# AphelionGroundStation.net
KiCad netlist of a schematic drawn in Altium Designer
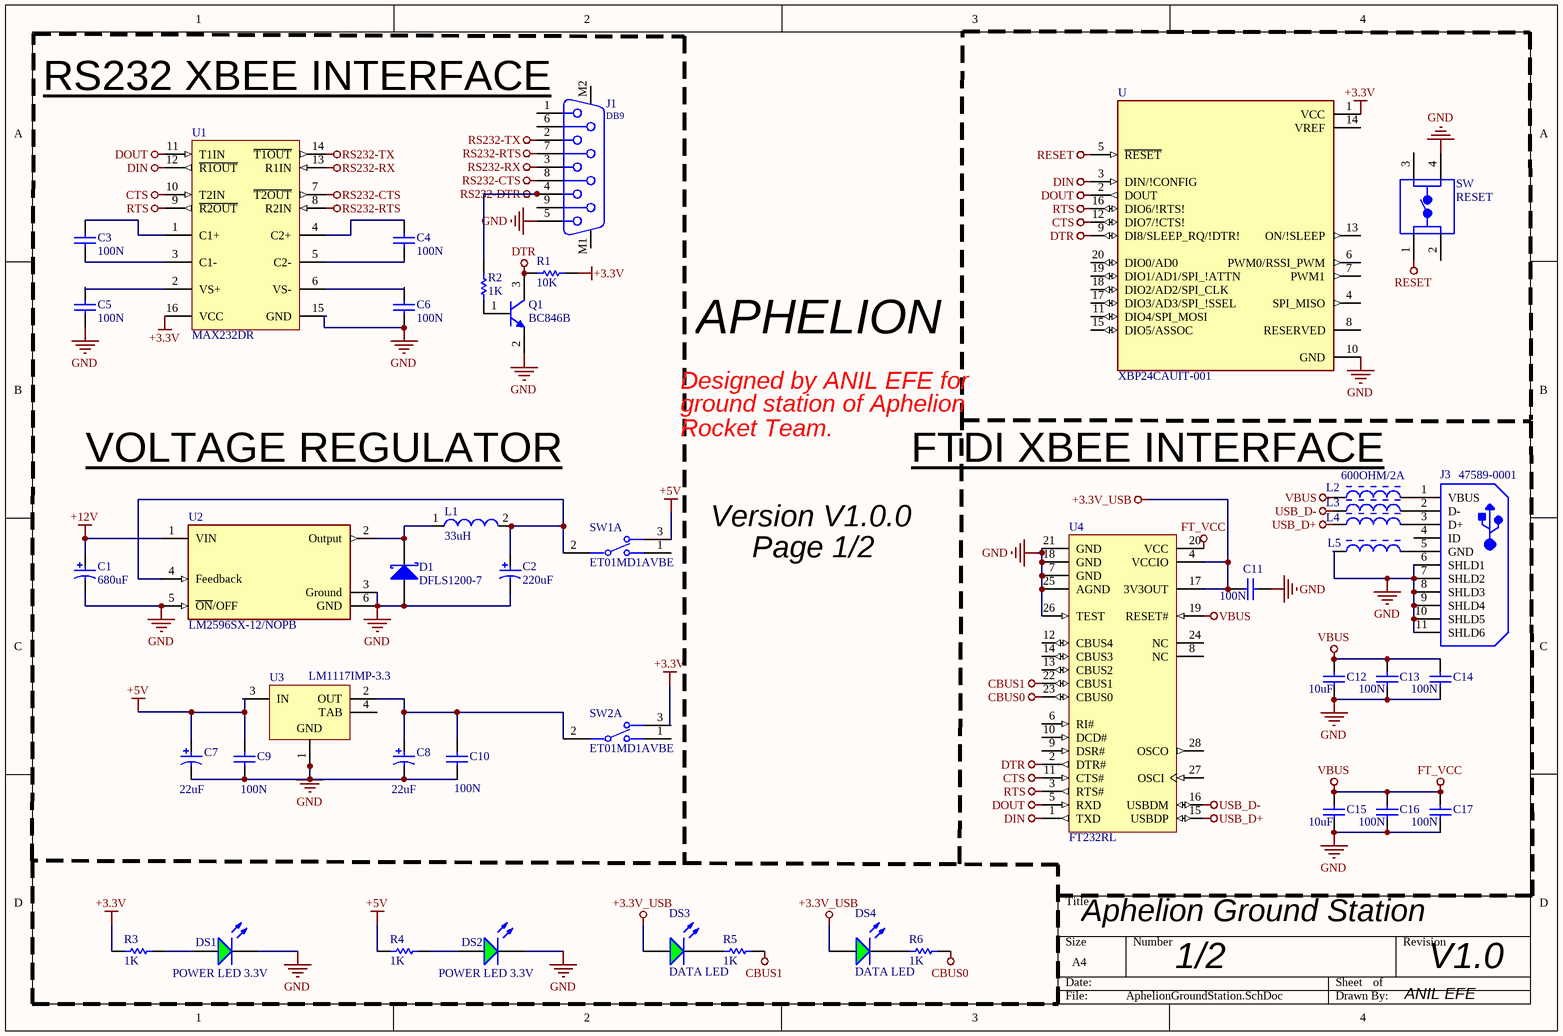
[diagram p0: AphelionGroundStation.SchDoc]

(export (version "E")
  (design (tool "Eeschema 10.0.6"))
  (components
    (comp (ref "C1")
      (value "680uF")
      (footprint "PNSC-FT-V-G_V")
      (fields (field (name "MANUFACTURER") "Panasonic"))
      (libsource (lib "Altium Content Vault") (part "CAP-P-2"))
    )
    (comp (ref "C2")
      (value "220uF")
      (footprint "PNSC-FP-V-F_V")
      (fields (field (name "MANUFACTURER") "Panasonic"))
      (libsource (lib "Altium Content Vault") (part "CAP-P-2"))
    )
    (comp (ref "C3")
      (value "100N")
      (footprint "KEMT-1206-2_M")
      (description "CAP, Ceramic, 0.1 uF, +/- 10%, 50 V, -55 to 125 degC, 1206 (3216 Metric), RoHS, Tape and Reel")
      (fields (field (name "MANUFACTURER") "Kemet"))
      (libsource (lib "Altium Content Vault") (part "CAP-NP-2"))
    )
    (comp (ref "C4")
      (value "100N")
      (footprint "KEMT-1206-2_M")
      (description "CAP, Ceramic, 0.1 uF, +/- 10%, 50 V, -55 to 125 degC, 1206 (3216 Metric), RoHS, Tape and Reel")
      (fields (field (name "MANUFACTURER") "Kemet"))
      (libsource (lib "Altium Content Vault") (part "CAP-NP-2"))
    )
    (comp (ref "C5")
      (value "100N")
      (footprint "KEMT-1206-2_M")
      (description "CAP, Ceramic, 0.1 uF, +/- 10%, 50 V, -55 to 125 degC, 1206 (3216 Metric), RoHS, Tape and Reel")
      (fields (field (name "MANUFACTURER") "Kemet"))
      (libsource (lib "Altium Content Vault") (part "CAP-NP-2"))
    )
    (comp (ref "C6")
      (value "100N")
      (footprint "KEMT-1206-2_M")
      (description "CAP, Ceramic, 0.1 uF, +/- 10%, 50 V, -55 to 125 degC, 1206 (3216 Metric), RoHS, Tape and Reel")
      (fields (field (name "MANUFACTURER") "Kemet"))
      (libsource (lib "Altium Content Vault") (part "CAP-NP-2"))
    )
    (comp (ref "C7")
      (value "22uF")
      (footprint "KEMT-T491-D_L")
      (fields (field (name "MANUFACTURER") "Kemet"))
      (libsource (lib "Altium Content Vault") (part "CAP-P-2"))
    )
    (comp (ref "C8")
      (value "22uF")
      (footprint "KEMT-T491-D_L")
      (fields (field (name "MANUFACTURER") "Kemet"))
      (libsource (lib "Altium Content Vault") (part "CAP-P-2"))
    )
    (comp (ref "C9")
      (value "100N")
      (footprint "KEMT-1206-2_M")
      (description "CAP, Ceramic, 0.1 uF, +/- 10%, 50 V, -55 to 125 degC, 1206 (3216 Metric), RoHS, Tape and Reel")
      (fields (field (name "MANUFACTURER") "Kemet"))
      (libsource (lib "Altium Content Vault") (part "CAP-NP-2"))
    )
    (comp (ref "C10")
      (value "100N")
      (footprint "KEMT-1206-2_M")
      (description "CAP, Ceramic, 0.1 uF, +/- 10%, 50 V, -55 to 125 degC, 1206 (3216 Metric), RoHS, Tape and Reel")
      (fields (field (name "MANUFACTURER") "Kemet"))
      (libsource (lib "Altium Content Vault") (part "CAP-NP-2"))
    )
    (comp (ref "C11")
      (value "100N")
      (footprint "KEMT-1206-2_M")
      (description "CAP, Ceramic, 0.1 uF, +/- 10%, 50 V, -55 to 125 degC, 1206 (3216 Metric), RoHS, Tape and Reel")
      (fields (field (name "MANUFACTURER") "Kemet"))
      (libsource (lib "Altium Content Vault") (part "CAP-NP-2"))
    )
    (comp (ref "C12")
      (value "10uF")
      (footprint "KEMT-1206-2_M")
      (description "CAP, Ceramic, 0.1 uF, +/- 10%, 50 V, -55 to 125 degC, 1206 (3216 Metric), RoHS, Tape and Reel")
      (fields (field (name "MANUFACTURER") "Kemet"))
      (libsource (lib "Altium Content Vault") (part "CAP-NP-2"))
    )
    (comp (ref "C13")
      (value "100N")
      (footprint "KEMT-1206-2_M")
      (description "CAP, Ceramic, 0.1 uF, +/- 10%, 50 V, -55 to 125 degC, 1206 (3216 Metric), RoHS, Tape and Reel")
      (fields (field (name "MANUFACTURER") "Kemet"))
      (libsource (lib "Altium Content Vault") (part "CAP-NP-2"))
    )
    (comp (ref "C14")
      (value "100N")
      (footprint "KEMT-1206-2_M")
      (description "CAP, Ceramic, 0.1 uF, +/- 10%, 50 V, -55 to 125 degC, 1206 (3216 Metric), RoHS, Tape and Reel")
      (fields (field (name "MANUFACTURER") "Kemet"))
      (libsource (lib "Altium Content Vault") (part "CAP-NP-2"))
    )
    (comp (ref "C15")
      (value "10uF")
      (footprint "KEMT-1206-2_M")
      (description "CAP, Ceramic, 0.1 uF, +/- 10%, 50 V, -55 to 125 degC, 1206 (3216 Metric), RoHS, Tape and Reel")
      (fields (field (name "MANUFACTURER") "Kemet"))
      (libsource (lib "Altium Content Vault") (part "CAP-NP-2"))
    )
    (comp (ref "C16")
      (value "100N")
      (footprint "KEMT-1206-2_M")
      (description "CAP, Ceramic, 0.1 uF, +/- 10%, 50 V, -55 to 125 degC, 1206 (3216 Metric), RoHS, Tape and Reel")
      (fields (field (name "MANUFACTURER") "Kemet"))
      (libsource (lib "Altium Content Vault") (part "CAP-NP-2"))
    )
    (comp (ref "C17")
      (value "100N")
      (footprint "KEMT-1206-2_M")
      (description "CAP, Ceramic, 0.1 uF, +/- 10%, 50 V, -55 to 125 degC, 1206 (3216 Metric), RoHS, Tape and Reel")
      (fields (field (name "MANUFACTURER") "Kemet"))
      (libsource (lib "Altium Content Vault") (part "CAP-NP-2"))
    )
    (comp (ref "D1")
      (value "DFLS1200-7")
      (footprint "DIOD-POWERDI123-2_A_V")
      (fields (field (name "MANUFACTURER") "Diodes Inc"))
      (libsource (lib "Altium Content Vault") (part "DSKY-AK-2"))
    )
    (comp (ref "DS1")
      (value "POWER LED 3.3V")
      (footprint "KING-APTD3216CGCK_V")
      (description "Chip LED Lamp, Green, 5 V, 30 mA, -40 to 85 degC, 2-Pin SMD, RoHS, Tape and Reel")
      (fields (field (name "MANUFACTURER") "Kingbright"))
      (libsource (lib "Altium Content Vault") (part "LED-GREEN-AK-2"))
    )
    (comp (ref "DS2")
      (value "POWER LED 3.3V")
      (footprint "KING-APTD3216CGCK_V")
      (description "Chip LED Lamp, Green, 5 V, 30 mA, -40 to 85 degC, 2-Pin SMD, RoHS, Tape and Reel")
      (fields (field (name "MANUFACTURER") "Kingbright"))
      (libsource (lib "Altium Content Vault") (part "LED-GREEN-AK-2"))
    )
    (comp (ref "DS3")
      (value "DATA LED")
      (footprint "KING-APTD3216CGCK_V")
      (description "Chip LED Lamp, Green, 5 V, 30 mA, -40 to 85 degC, 2-Pin SMD, RoHS, Tape and Reel")
      (fields (field (name "MANUFACTURER") "Kingbright"))
      (libsource (lib "Altium Content Vault") (part "LED-GREEN-AK-2"))
    )
    (comp (ref "DS4")
      (value "DATA LED")
      (footprint "KING-APTD3216CGCK_V")
      (description "Chip LED Lamp, Green, 5 V, 30 mA, -40 to 85 degC, 2-Pin SMD, RoHS, Tape and Reel")
      (fields (field (name "MANUFACTURER") "Kingbright"))
      (libsource (lib "Altium Content Vault") (part "LED-GREEN-AK-2"))
    )
    (comp (ref "J1")
      (value "DB9")
      (footprint "618009231321")
      (description "Female PCB Connector with Hex Screw WR-DSUB, 10.30 mm, Angled, 9 pins")
      (fields
        (field (name "PART NUMBER") "618009231321")
        (field (name "MANUFACTURER") "Wurth Elektronik")
        (field (name "PUBLISHER") "WurthElektronik")
      )
      (libsource (lib "Altium Content Vault") (part "WE-CN-2S-2F-D9"))
    )
    (comp (ref "J3")
      (value "47589-0001")
      (footprint "MOLX-47589-0001_V")
      (description "Right Angle Female Type AB Micro USB Connector, 30 V, 1.8 A, -30 to 85 degC, RoHS, Tape and Reel")
      (fields (field (name "MANUFACTURER") "Molex"))
      (libsource (lib "Altium Content Vault") (part "USB-5-6SHLD"))
    )
    (comp (ref "L1")
      (value "33uH")
      (footprint "WE-PD 1050")
      (description "SMD-Shielded Power Inductor WE-PD, L=33.0 µH")
      (fields (field (name "PARTNUMBER") "7447714330") (field (name "MANUFACTURER") "Wuerth Elektronik"))
      (libsource (lib "Altium Content Vault") (part "PAS-IND-INDUCTOR-2"))
    )
    (comp (ref "L2")
      (value "600OHM/2A")
      (footprint "MURA-BLM31A_L")
      (description "Chip Bead, 100 MHz, 200 mA, -55 to 125 degC, 2-Pin SMD (1206), RoHS, Tape and Reel")
      (fields (field (name "MANUFACTURER") "Murata") (field (name "TOLERANCE") "25%"))
      (libsource (lib "Altium Content Vault") (part "IND-FB-2"))
    )
    (comp (ref "L3")
      (value "600OHM/2A")
      (footprint "MURA-BLM31A_L")
      (description "Chip Bead, 100 MHz, 200 mA, -55 to 125 degC, 2-Pin SMD (1206), RoHS, Tape and Reel")
      (fields (field (name "MANUFACTURER") "Murata") (field (name "TOLERANCE") "25%"))
      (libsource (lib "Altium Content Vault") (part "IND-FB-2"))
    )
    (comp (ref "L4")
      (value "600OHM/2A")
      (footprint "MURA-BLM31A_L")
      (description "Chip Bead, 100 MHz, 200 mA, -55 to 125 degC, 2-Pin SMD (1206), RoHS, Tape and Reel")
      (fields (field (name "MANUFACTURER") "Murata") (field (name "TOLERANCE") "25%"))
      (libsource (lib "Altium Content Vault") (part "IND-FB-2"))
    )
    (comp (ref "L5")
      (value "600OHM/2A")
      (footprint "MURA-BLM31A_L")
      (description "Chip Bead, 100 MHz, 200 mA, -55 to 125 degC, 2-Pin SMD (1206), RoHS, Tape and Reel")
      (fields (field (name "MANUFACTURER") "Murata") (field (name "TOLERANCE") "25%"))
      (libsource (lib "Altium Content Vault") (part "IND-FB-2"))
    )
    (comp (ref "Q1")
      (value "BC846B")
      (footprint "ONSC-SOT-23-3-318-08_V")
      (description "General Purpose Transistor, NPN Silicon, 3-Pin SOT-23, Pb-Free, Tape and Reel")
      (fields (field (name "PARTNUMBER") "BC846BLT1G") (field (name "MANUFACTURER") "On Semiconductor"))
      (libsource (lib "Altium Content Vault") (part "ONSC-NPN-B1E2C3-3"))
    )
    (comp (ref "R1")
      (value "10K")
      (footprint "RESC3216X60X45LL10T20")
      (fields (field (name "MANUFACTURER") "Vishay Dale") (field (name "PART NUMBER") "CRCW12064M70FKEA"))
      (libsource (lib "Altium Content Vault") (part "RES"))
    )
    (comp (ref "R2")
      (value "1K")
      (footprint "RESC3216X60X45LL10T20")
      (fields (field (name "MANUFACTURER") "Vishay Dale") (field (name "PART NUMBER") "CRCW12064M70FKEA"))
      (libsource (lib "Altium Content Vault") (part "RES"))
    )
    (comp (ref "R3")
      (value "1K")
      (footprint "RESC3216X60X45LL10T20")
      (fields (field (name "MANUFACTURER") "Vishay Dale") (field (name "PART NUMBER") "CRCW12064M70FKEA"))
      (libsource (lib "Altium Content Vault") (part "RES"))
    )
    (comp (ref "R4")
      (value "1K")
      (footprint "RESC3216X60X45LL10T20")
      (fields (field (name "MANUFACTURER") "Vishay Dale") (field (name "PART NUMBER") "CRCW12064M70FKEA"))
      (libsource (lib "Altium Content Vault") (part "RES"))
    )
    (comp (ref "R5")
      (value "1K")
      (footprint "RESC3216X60X45LL10T20")
      (fields (field (name "MANUFACTURER") "Vishay Dale") (field (name "PART NUMBER") "CRCW12064M70FKEA"))
      (libsource (lib "Altium Content Vault") (part "RES"))
    )
    (comp (ref "R6")
      (value "1K")
      (footprint "RESC3216X60X45LL10T20")
      (fields (field (name "MANUFACTURER") "Vishay Dale") (field (name "PART NUMBER") "CRCW12064M70FKEA"))
      (libsource (lib "Altium Content Vault") (part "RES"))
    )
    (comp (ref "SW")
      (value "RESET")
      (footprint "TE_3-1825910-1")
      (description "Switch Push Button OFF _ON_ SPST Round Button 0.05A 24VDC Momentary Contact PC Pins Thru-Hole")
      (fields (field (name "MF") "TE Connectivity") (field (name "MP") "3-1825910-1"))
      (libsource (lib "3-1825910-1 (2)") (part "3-1825910-1"))
    )
    (comp (ref "SW1")
      (value "ET01MD1AVBE")
      (footprint "FP-ET01MD1AVBE-MFG")
      (description "SWITCH TOGGLE SPDT 0.4VA 20V")
      (fields
        (field (name "MANUFACTURER") "C&K Components")
        (field (name "OCTOPART") "https://octopart.com/et01md1avbe-c%26k+components-2490750")
      )
      (libsource (lib "Altium Content Vault") (part "747ed32133a6b33bcee331fbe50a995"))
    )
    (comp (ref "SW2")
      (value "ET01MD1AVBE")
      (footprint "FP-ET01MD1AVBE-MFG")
      (description "SWITCH TOGGLE SPDT 0.4VA 20V")
      (fields
        (field (name "MANUFACTURER") "C&K Components")
        (field (name "OCTOPART") "https://octopart.com/et01md1avbe-c%26k+components-2490750")
      )
      (libsource (lib "Altium Content Vault") (part "747ed32133a6b33bcee331fbe50a995"))
    )
    (comp (ref "U")
      (value "XBP24CAUIT-001")
      (footprint "MODULE_XBP24CAUIT-001")
      (description "802.15.4 Transceiver Module 2.4GHz Antenna Not Included, U.FL Through Hole")
      (fields (field (name "MF") "Digi International"))
      (libsource (lib "XBP24CAUIT-001") (part "XBP24CAUIT-001"))
    )
    (comp (ref "U1")
      (value "MAX232DR")
      (footprint "D0016A_L")
      (description "Dual EIA-232 Driver / Receiver, 0 to 70 degC, 16-Pin SOIC (D), Green (RoHS & no Sb/Br)")
      (libsource (lib "Altium Content Vault") (part "TI-MAX232-SOIC_D-16"))
    )
    (comp (ref "U2")
      (value "LM2596SX-12/NOPB")
      (footprint "FP-KTT0005B-MFG")
      (description "IC REG BUCK 12V 3A TO263-5")
      (fields
        (field (name "MANUFACTURER") "Texas Instruments")
        (field (name "OCTOPART") "https://octopart.com/lm2596sx-12%2Fnopb-texas+instruments-24812942")
      )
      (libsource (lib "Altium Content Vault") (part "a9e8fb2209d2d0c16097fdaefd4ac2b"))
    )
    (comp (ref "U3")
      (value "LM1117IMP-3.3")
      (footprint "DCY0004A_N")
      (description "800mA Low-Dropout Linear Regulator, 4-pin SOT-223, Pb-Free")
      (fields
        (field (name "PARTNUMBER") "LM1117IMP-3.3/NOPB")
        (field (name "MANUFACTURER") "Texas Instruments")
      )
      (libsource (lib "Altium Content Vault") (part "PM-REG-LM1086-SOT4"))
    )
    (comp (ref "U4")
      (value "FT232RL")
      (footprint "FTDI-SSOP-28_M")
      (description "IC USB FS SERIAL UART 28-SSOP")
      (fields (field (name "MANUFACTURER") "FTDI"))
      (libsource (lib "Altium Content Vault") (part "FTDI-FT232-SSOP-28"))
    )
  )
  (nets
    (net (code "1") (name "+3.3V") (class "Default")
      (node (ref "R1") (pin "2") (pinfunction "2_2") (pintype "passive"))
      (node (ref "R3") (pin "1") (pinfunction "1_1") (pintype "passive"))
      (node (ref "SW2") (pin "3") (pinfunction "3_3") (pintype "passive"))
      (node (ref "U") (pin "1") (pinfunction "VCC_1") (pintype "power_in"))
      (node (ref "U1") (pin "16") (pinfunction "VCC_16") (pintype "power_in"))
    )
    (net (code "2") (name "+3.3V_USB") (class "Default")
      (node (ref "C11") (pin "2") (pinfunction "2_2") (pintype "passive"))
      (node (ref "DS3") (pin "1") (pinfunction "A_1") (pintype "passive"))
      (node (ref "DS4") (pin "1") (pinfunction "A_1") (pintype "passive"))
      (node (ref "U4") (pin "17") (pinfunction "3V3OUT_17") (pintype "power_in"))
      (node (ref "U4") (pin "4") (pinfunction "VCCIO_4") (pintype "power_in"))
    )
    (net (code "3") (name "+5V") (class "Default")
      (node (ref "C7") (pin "1") (pinfunction "1_1") (pintype "passive"))
      (node (ref "C9") (pin "2") (pinfunction "2_2") (pintype "passive"))
      (node (ref "R4") (pin "1") (pinfunction "1_1") (pintype "passive"))
      (node (ref "SW1") (pin "3") (pinfunction "3_3") (pintype "passive"))
      (node (ref "U3") (pin "3") (pinfunction "IN_3") (pintype "power_in"))
    )
    (net (code "4") (name "+12V") (class "Default")
      (node (ref "C1") (pin "1") (pinfunction "1_1") (pintype "passive"))
      (node (ref "U2") (pin "1") (pinfunction "VIN_1") (pintype "power_in"))
    )
    (net (code "5") (name "CBUS0") (class "Default")
      (node (ref "R6") (pin "2") (pinfunction "2_2") (pintype "passive"))
      (node (ref "U4") (pin "23") (pinfunction "CBUS0_23") (pintype "bidirectional"))
    )
    (net (code "6") (name "CBUS1") (class "Default")
      (node (ref "R5") (pin "2") (pinfunction "2_2") (pintype "passive"))
      (node (ref "U4") (pin "22") (pinfunction "CBUS1_22") (pintype "bidirectional"))
    )
    (net (code "7") (name "CTS") (class "Default")
      (node (ref "U") (pin "12") (pinfunction "DIO7/!CTS!_12") (pintype "bidirectional"))
      (node (ref "U1") (pin "10") (pinfunction "T2IN_10") (pintype "input"))
      (node (ref "U4") (pin "11") (pinfunction "CTS#_11") (pintype "input"))
    )
    (net (code "8") (name "DIN") (class "Default")
      (node (ref "U") (pin "3") (pinfunction "DIN/!CONFIG_3") (pintype "input"))
      (node (ref "U1") (pin "12") (pinfunction "~{R1OUT}_12") (pintype "output"))
      (node (ref "U4") (pin "1") (pinfunction "TXD_1") (pintype "output"))
    )
    (net (code "9") (name "DOUT") (class "Default")
      (node (ref "U") (pin "2") (pinfunction "DOUT_2") (pintype "output"))
      (node (ref "U1") (pin "11") (pinfunction "T1IN_11") (pintype "input"))
      (node (ref "U4") (pin "5") (pinfunction "RXD_5") (pintype "input"))
    )
    (net (code "10") (name "DTR") (class "Default")
      (node (ref "Q1") (pin "3") (pinfunction "C_3") (pintype "passive"))
      (node (ref "R1") (pin "1") (pinfunction "1_1") (pintype "passive"))
      (node (ref "U") (pin "9") (pinfunction "DI8/SLEEP_RQ/!DTR!_9") (pintype "bidirectional"))
      (node (ref "U4") (pin "2") (pinfunction "DTR#_2") (pintype "output"))
    )
    (net (code "11") (name "FT_VCC") (class "Default")
      (node (ref "C12") (pin "2") (pinfunction "2_2") (pintype "passive"))
      (node (ref "C13") (pin "2") (pinfunction "2_2") (pintype "passive"))
      (node (ref "C14") (pin "2") (pinfunction "2_2") (pintype "passive"))
      (node (ref "C15") (pin "2") (pinfunction "2_2") (pintype "passive"))
      (node (ref "C16") (pin "2") (pinfunction "2_2") (pintype "passive"))
      (node (ref "C17") (pin "2") (pinfunction "2_2") (pintype "passive"))
      (node (ref "L2") (pin "1") (pinfunction "1_1") (pintype "passive"))
      (node (ref "U4") (pin "19") (pinfunction "RESET#_19") (pintype "input"))
      (node (ref "U4") (pin "20") (pinfunction "VCC_20") (pintype "power_in"))
    )
    (net (code "12") (name "GND") (class "Default")
      (node (ref "C1") (pin "2") (pinfunction "2_2") (pintype "passive"))
      (node (ref "C10") (pin "1") (pinfunction "1_1") (pintype "passive"))
      (node (ref "C11") (pin "1") (pinfunction "1_1") (pintype "passive"))
      (node (ref "C12") (pin "1") (pinfunction "1_1") (pintype "passive"))
      (node (ref "C13") (pin "1") (pinfunction "1_1") (pintype "passive"))
      (node (ref "C14") (pin "1") (pinfunction "1_1") (pintype "passive"))
      (node (ref "C15") (pin "1") (pinfunction "1_1") (pintype "passive"))
      (node (ref "C16") (pin "1") (pinfunction "1_1") (pintype "passive"))
      (node (ref "C17") (pin "1") (pinfunction "1_1") (pintype "passive"))
      (node (ref "C2") (pin "2") (pinfunction "2_2") (pintype "passive"))
      (node (ref "C5") (pin "2") (pinfunction "2_2") (pintype "passive"))
      (node (ref "C6") (pin "2") (pinfunction "2_2") (pintype "passive"))
      (node (ref "C7") (pin "2") (pinfunction "2_2") (pintype "passive"))
      (node (ref "C8") (pin "2") (pinfunction "2_2") (pintype "passive"))
      (node (ref "C9") (pin "1") (pinfunction "1_1") (pintype "passive"))
      (node (ref "D1") (pin "1") (pinfunction "A_1") (pintype "passive"))
      (node (ref "DS1") (pin "2") (pinfunction "K_2") (pintype "passive"))
      (node (ref "DS2") (pin "2") (pinfunction "K_2") (pintype "passive"))
      (node (ref "J1") (pin "5") (pinfunction "5_5") (pintype "passive"))
      (node (ref "J3") (pin "10") (pinfunction "SHLD5_10") (pintype "passive"))
      (node (ref "J3") (pin "11") (pinfunction "SHLD6_11") (pintype "passive"))
      (node (ref "J3") (pin "6") (pinfunction "SHLD1_6") (pintype "passive"))
      (node (ref "J3") (pin "7") (pinfunction "SHLD2_7") (pintype "passive"))
      (node (ref "J3") (pin "8") (pinfunction "SHLD3_8") (pintype "passive"))
      (node (ref "J3") (pin "9") (pinfunction "SHLD4_9") (pintype "passive"))
      (node (ref "L5") (pin "1") (pinfunction "1_1") (pintype "passive"))
      (node (ref "Q1") (pin "2") (pinfunction "E_2") (pintype "passive"))
      (node (ref "SW") (pin "4") (pinfunction "4_4") (pintype "passive"))
      (node (ref "U") (pin "10") (pinfunction "GND_10") (pintype "power_in"))
      (node (ref "U1") (pin "15") (pinfunction "GND_15") (pintype "power_in"))
      (node (ref "U2") (pin "3") (pinfunction "Ground_3") (pintype "power_in"))
      (node (ref "U2") (pin "5") (pinfunction "~{ON}/OFF_5") (pintype "input"))
      (node (ref "U2") (pin "6") (pinfunction "GND_6") (pintype "power_in"))
      (node (ref "U3") (pin "1") (pinfunction "GND_1") (pintype "power_in"))
      (node (ref "U4") (pin "18") (pinfunction "GND_18") (pintype "power_in"))
      (node (ref "U4") (pin "21") (pinfunction "GND_21") (pintype "power_in"))
      (node (ref "U4") (pin "25") (pinfunction "AGND_25") (pintype "power_in"))
      (node (ref "U4") (pin "26") (pinfunction "TEST_26") (pintype "input"))
      (node (ref "U4") (pin "7") (pinfunction "GND_7") (pintype "power_in"))
    )
    (net (code "13") (name "Net-(D1-K)") (class "Default")
      (node (ref "D1") (pin "2") (pinfunction "K_2") (pintype "passive"))
      (node (ref "L1") (pin "1") (pinfunction "1_1") (pintype "passive"))
      (node (ref "U2") (pin "2") (pinfunction "Output_2") (pintype "output"))
    )
    (net (code "14") (name "Net-(DS1-A)") (class "Default")
      (node (ref "DS1") (pin "1") (pinfunction "A_1") (pintype "passive"))
      (node (ref "R3") (pin "2") (pinfunction "2_2") (pintype "passive"))
    )
    (net (code "15") (name "Net-(DS2-A)") (class "Default")
      (node (ref "DS2") (pin "1") (pinfunction "A_1") (pintype "passive"))
      (node (ref "R4") (pin "2") (pinfunction "2_2") (pintype "passive"))
    )
    (net (code "16") (name "Net-(DS3-K)") (class "Default")
      (node (ref "DS3") (pin "2") (pinfunction "K_2") (pintype "passive"))
      (node (ref "R5") (pin "1") (pinfunction "1_1") (pintype "passive"))
    )
    (net (code "17") (name "Net-(DS4-K)") (class "Default")
      (node (ref "DS4") (pin "2") (pinfunction "K_2") (pintype "passive"))
      (node (ref "R6") (pin "1") (pinfunction "1_1") (pintype "passive"))
    )
    (net (code "18") (name "Net-(J3-D+)") (class "Default")
      (node (ref "J3") (pin "3") (pinfunction "D+_3") (pintype "passive"))
      (node (ref "L4") (pin "2") (pinfunction "2_2") (pintype "passive"))
    )
    (net (code "19") (name "Net-(J3-D-)") (class "Default")
      (node (ref "J3") (pin "2") (pinfunction "D-_2") (pintype "passive"))
      (node (ref "L3") (pin "2") (pinfunction "2_2") (pintype "passive"))
    )
    (net (code "20") (name "Net-(J3-GND)") (class "Default")
      (node (ref "J3") (pin "5") (pinfunction "GND_5") (pintype "passive"))
      (node (ref "L5") (pin "2") (pinfunction "2_2") (pintype "passive"))
    )
    (net (code "21") (name "Net-(J3-VBUS)") (class "Default")
      (node (ref "J3") (pin "1") (pinfunction "VBUS_1") (pintype "passive"))
      (node (ref "L2") (pin "2") (pinfunction "2_2") (pintype "passive"))
    )
    (net (code "22") (name "Net-(Q1-B)") (class "Default")
      (node (ref "Q1") (pin "1") (pinfunction "B_1") (pintype "passive"))
      (node (ref "R2") (pin "1") (pinfunction "1_1") (pintype "passive"))
    )
    (net (code "23") (name "Net-(SW1A-COM)") (class "Default")
      (node (ref "C2") (pin "1") (pinfunction "1_1") (pintype "passive"))
      (node (ref "L1") (pin "2") (pinfunction "2_2") (pintype "passive"))
      (node (ref "SW1") (pin "2") (pinfunction "COM_2") (pintype "passive"))
      (node (ref "U2") (pin "4") (pinfunction "Feedback_4") (pintype "input"))
    )
    (net (code "24") (name "Net-(SW2A-COM)") (class "Default")
      (node (ref "C10") (pin "2") (pinfunction "2_2") (pintype "passive"))
      (node (ref "C8") (pin "1") (pinfunction "1_1") (pintype "passive"))
      (node (ref "SW2") (pin "2") (pinfunction "COM_2") (pintype "passive"))
      (node (ref "U3") (pin "2") (pinfunction "OUT_2") (pintype "power_in"))
    )
    (net (code "25") (name "Net-(U1-C1+)") (class "Default")
      (node (ref "C3") (pin "2") (pinfunction "2_2") (pintype "passive"))
      (node (ref "U1") (pin "1") (pinfunction "C1+_1") (pintype "passive"))
    )
    (net (code "26") (name "Net-(U1-C1-)") (class "Default")
      (node (ref "C3") (pin "1") (pinfunction "1_1") (pintype "passive"))
      (node (ref "U1") (pin "3") (pinfunction "C1-_3") (pintype "passive"))
    )
    (net (code "27") (name "Net-(U1-C2+)") (class "Default")
      (node (ref "C4") (pin "2") (pinfunction "2_2") (pintype "passive"))
      (node (ref "U1") (pin "4") (pinfunction "C2+_4") (pintype "passive"))
    )
    (net (code "28") (name "Net-(U1-C2-)") (class "Default")
      (node (ref "C4") (pin "1") (pinfunction "1_1") (pintype "passive"))
      (node (ref "U1") (pin "5") (pinfunction "C2-_5") (pintype "passive"))
    )
    (net (code "29") (name "Net-(U1-VS+)") (class "Default")
      (node (ref "C5") (pin "1") (pinfunction "1_1") (pintype "passive"))
      (node (ref "U1") (pin "2") (pinfunction "VS+_2") (pintype "power_in"))
    )
    (net (code "30") (name "Net-(U1-VS-)") (class "Default")
      (node (ref "C6") (pin "1") (pinfunction "1_1") (pintype "passive"))
      (node (ref "U1") (pin "6") (pinfunction "VS-_6") (pintype "power_in"))
    )
    (net (code "31") (name "RESET") (class "Default")
      (node (ref "SW") (pin "1") (pinfunction "1_1") (pintype "passive"))
      (node (ref "U") (pin "5") (pinfunction "~{RESET}_5") (pintype "input"))
    )
    (net (code "32") (name "RS232-CTS") (class "Default")
      (node (ref "J1") (pin "8") (pinfunction "8_8") (pintype "passive"))
      (node (ref "U1") (pin "7") (pinfunction "~{T2OUT}_7") (pintype "output"))
    )
    (net (code "33") (name "RS232-DTR") (class "Default")
      (node (ref "J1") (pin "4") (pinfunction "4_4") (pintype "passive"))
      (node (ref "R2") (pin "2") (pinfunction "2_2") (pintype "passive"))
    )
    (net (code "34") (name "RS232-RTS") (class "Default")
      (node (ref "J1") (pin "7") (pinfunction "7_7") (pintype "passive"))
      (node (ref "U1") (pin "8") (pinfunction "R2IN_8") (pintype "input"))
    )
    (net (code "35") (name "RS232-RX") (class "Default")
      (node (ref "J1") (pin "3") (pinfunction "3_3") (pintype "passive"))
      (node (ref "U1") (pin "13") (pinfunction "R1IN_13") (pintype "input"))
    )
    (net (code "36") (name "RS232-TX") (class "Default")
      (node (ref "J1") (pin "2") (pinfunction "2_2") (pintype "passive"))
      (node (ref "U1") (pin "14") (pinfunction "~{T1OUT}_14") (pintype "output"))
    )
    (net (code "37") (name "RTS") (class "Default")
      (node (ref "U") (pin "16") (pinfunction "DIO6/!RTS!_16") (pintype "bidirectional"))
      (node (ref "U1") (pin "9") (pinfunction "~{R2OUT}_9") (pintype "output"))
      (node (ref "U4") (pin "3") (pinfunction "RTS#_3") (pintype "output"))
    )
    (net (code "38") (name "USB_D+") (class "Default")
      (node (ref "L4") (pin "1") (pinfunction "1_1") (pintype "passive"))
      (node (ref "U4") (pin "15") (pinfunction "USBDP_15") (pintype "bidirectional"))
    )
    (net (code "39") (name "USB_D-") (class "Default")
      (node (ref "L3") (pin "1") (pinfunction "1_1") (pintype "passive"))
      (node (ref "U4") (pin "16") (pinfunction "USBDM_16") (pintype "bidirectional"))
    )
    (net (code "40") (name "unconnected-(J1-Pad1)") (class "Default")
      (node (ref "J1") (pin "1") (pinfunction "1_1") (pintype "passive"))
    )
    (net (code "41") (name "unconnected-(J1-Pad6)") (class "Default")
      (node (ref "J1") (pin "6") (pinfunction "6_6") (pintype "passive"))
    )
    (net (code "42") (name "unconnected-(J1-Pad9)") (class "Default")
      (node (ref "J1") (pin "9") (pinfunction "9_9") (pintype "passive"))
    )
    (net (code "43") (name "unconnected-(J1-PadM1)") (class "Default")
      (node (ref "J1") (pin "M1") (pinfunction "M1_M1") (pintype "passive"))
    )
    (net (code "44") (name "unconnected-(J1-PadM2)") (class "Default")
      (node (ref "J1") (pin "M2") (pinfunction "M2_M2") (pintype "passive"))
    )
    (net (code "45") (name "unconnected-(J3-ID-Pad4)") (class "Default")
      (node (ref "J3") (pin "4") (pinfunction "ID_4") (pintype "passive"))
    )
    (net (code "46") (name "unconnected-(SW-Pad2)") (class "Default")
      (node (ref "SW") (pin "2") (pinfunction "2_2") (pintype "passive"))
    )
    (net (code "47") (name "unconnected-(SW-Pad3)") (class "Default")
      (node (ref "SW") (pin "3") (pinfunction "3_3") (pintype "passive"))
    )
    (net (code "48") (name "unconnected-(SW1-Pad1)") (class "Default")
      (node (ref "SW1") (pin "1") (pinfunction "1_1") (pintype "passive"))
    )
    (net (code "49") (name "unconnected-(SW2-Pad1)") (class "Default")
      (node (ref "SW2") (pin "1") (pinfunction "1_1") (pintype "passive"))
    )
    (net (code "50") (name "unconnected-(U-DIO0{slash}AD0-Pad20)") (class "Default")
      (node (ref "U") (pin "20") (pinfunction "DIO0/AD0_20") (pintype "bidirectional"))
    )
    (net (code "51") (name "unconnected-(U-DIO1{slash}AD1{slash}SPI_!ATTN-Pad19)") (class "Default")
      (node (ref "U") (pin "19") (pinfunction "DIO1/AD1/SPI_!ATTN_19") (pintype "bidirectional"))
    )
    (net (code "52") (name "unconnected-(U-DIO2{slash}AD2{slash}SPI_CLK-Pad18)") (class "Default")
      (node (ref "U") (pin "18") (pinfunction "DIO2/AD2/SPI_CLK_18") (pintype "bidirectional"))
    )
    (net (code "53") (name "unconnected-(U-DIO3{slash}AD3{slash}SPI_!SSEL-Pad17)") (class "Default")
      (node (ref "U") (pin "17") (pinfunction "DIO3/AD3/SPI_!SSEL_17") (pintype "bidirectional"))
    )
    (net (code "54") (name "unconnected-(U-DIO4{slash}SPI_MOSI-Pad11)") (class "Default")
      (node (ref "U") (pin "11") (pinfunction "DIO4/SPI_MOSI_11") (pintype "bidirectional"))
    )
    (net (code "55") (name "unconnected-(U-DIO5{slash}ASSOC-Pad15)") (class "Default")
      (node (ref "U") (pin "15") (pinfunction "DIO5/ASSOC_15") (pintype "bidirectional"))
    )
    (net (code "56") (name "unconnected-(U-ON{slash}!SLEEP-Pad13)") (class "Default")
      (node (ref "U") (pin "13") (pinfunction "ON/!SLEEP_13") (pintype "output"))
    )
    (net (code "57") (name "unconnected-(U-PWM0{slash}RSSI_PWM-Pad6)") (class "Default")
      (node (ref "U") (pin "6") (pinfunction "PWM0/RSSI_PWM_6") (pintype "output"))
    )
    (net (code "58") (name "unconnected-(U-PWM1-Pad7)") (class "Default")
      (node (ref "U") (pin "7") (pinfunction "PWM1_7") (pintype "output"))
    )
    (net (code "59") (name "unconnected-(U-RESERVED-Pad8)") (class "Default")
      (node (ref "U") (pin "8") (pinfunction "RESERVED_8") (pintype "passive"))
    )
    (net (code "60") (name "unconnected-(U-SPI_MISO-Pad4)") (class "Default")
      (node (ref "U") (pin "4") (pinfunction "SPI_MISO_4") (pintype "output"))
    )
    (net (code "61") (name "unconnected-(U-VREF-Pad14)") (class "Default")
      (node (ref "U") (pin "14") (pinfunction "VREF_14") (pintype "power_in"))
    )
    (net (code "62") (name "unconnected-(U3-TAB-Pad4)") (class "Default")
      (node (ref "U3") (pin "4") (pinfunction "TAB_4") (pintype "power_in"))
    )
    (net (code "63") (name "unconnected-(U4-CBUS2-Pad13)") (class "Default")
      (node (ref "U4") (pin "13") (pinfunction "CBUS2_13") (pintype "bidirectional"))
    )
    (net (code "64") (name "unconnected-(U4-CBUS3-Pad14)") (class "Default")
      (node (ref "U4") (pin "14") (pinfunction "CBUS3_14") (pintype "bidirectional"))
    )
    (net (code "65") (name "unconnected-(U4-CBUS4-Pad12)") (class "Default")
      (node (ref "U4") (pin "12") (pinfunction "CBUS4_12") (pintype "bidirectional"))
    )
    (net (code "66") (name "unconnected-(U4-DCD#-Pad10)") (class "Default")
      (node (ref "U4") (pin "10") (pinfunction "DCD#_10") (pintype "input"))
    )
    (net (code "67") (name "unconnected-(U4-DSR#-Pad9)") (class "Default")
      (node (ref "U4") (pin "9") (pinfunction "DSR#_9") (pintype "input"))
    )
    (net (code "68") (name "unconnected-(U4-NC-Pad8)") (class "Default")
      (node (ref "U4") (pin "8") (pinfunction "NC_8") (pintype "passive"))
    )
    (net (code "69") (name "unconnected-(U4-NC-Pad24)") (class "Default")
      (node (ref "U4") (pin "24") (pinfunction "NC_24") (pintype "passive"))
    )
    (net (code "70") (name "unconnected-(U4-OSCI-Pad27)") (class "Default")
      (node (ref "U4") (pin "27") (pinfunction "OSCI_27") (pintype "input"))
    )
    (net (code "71") (name "unconnected-(U4-OSCO-Pad28)") (class "Default")
      (node (ref "U4") (pin "28") (pinfunction "OSCO_28") (pintype "output"))
    )
    (net (code "72") (name "unconnected-(U4-RI#-Pad6)") (class "Default")
      (node (ref "U4") (pin "6") (pinfunction "RI#_6") (pintype "input"))
    )
  )
)
